# toucanRev2.net
KiCad netlist of a schematic drawn in EAGLE
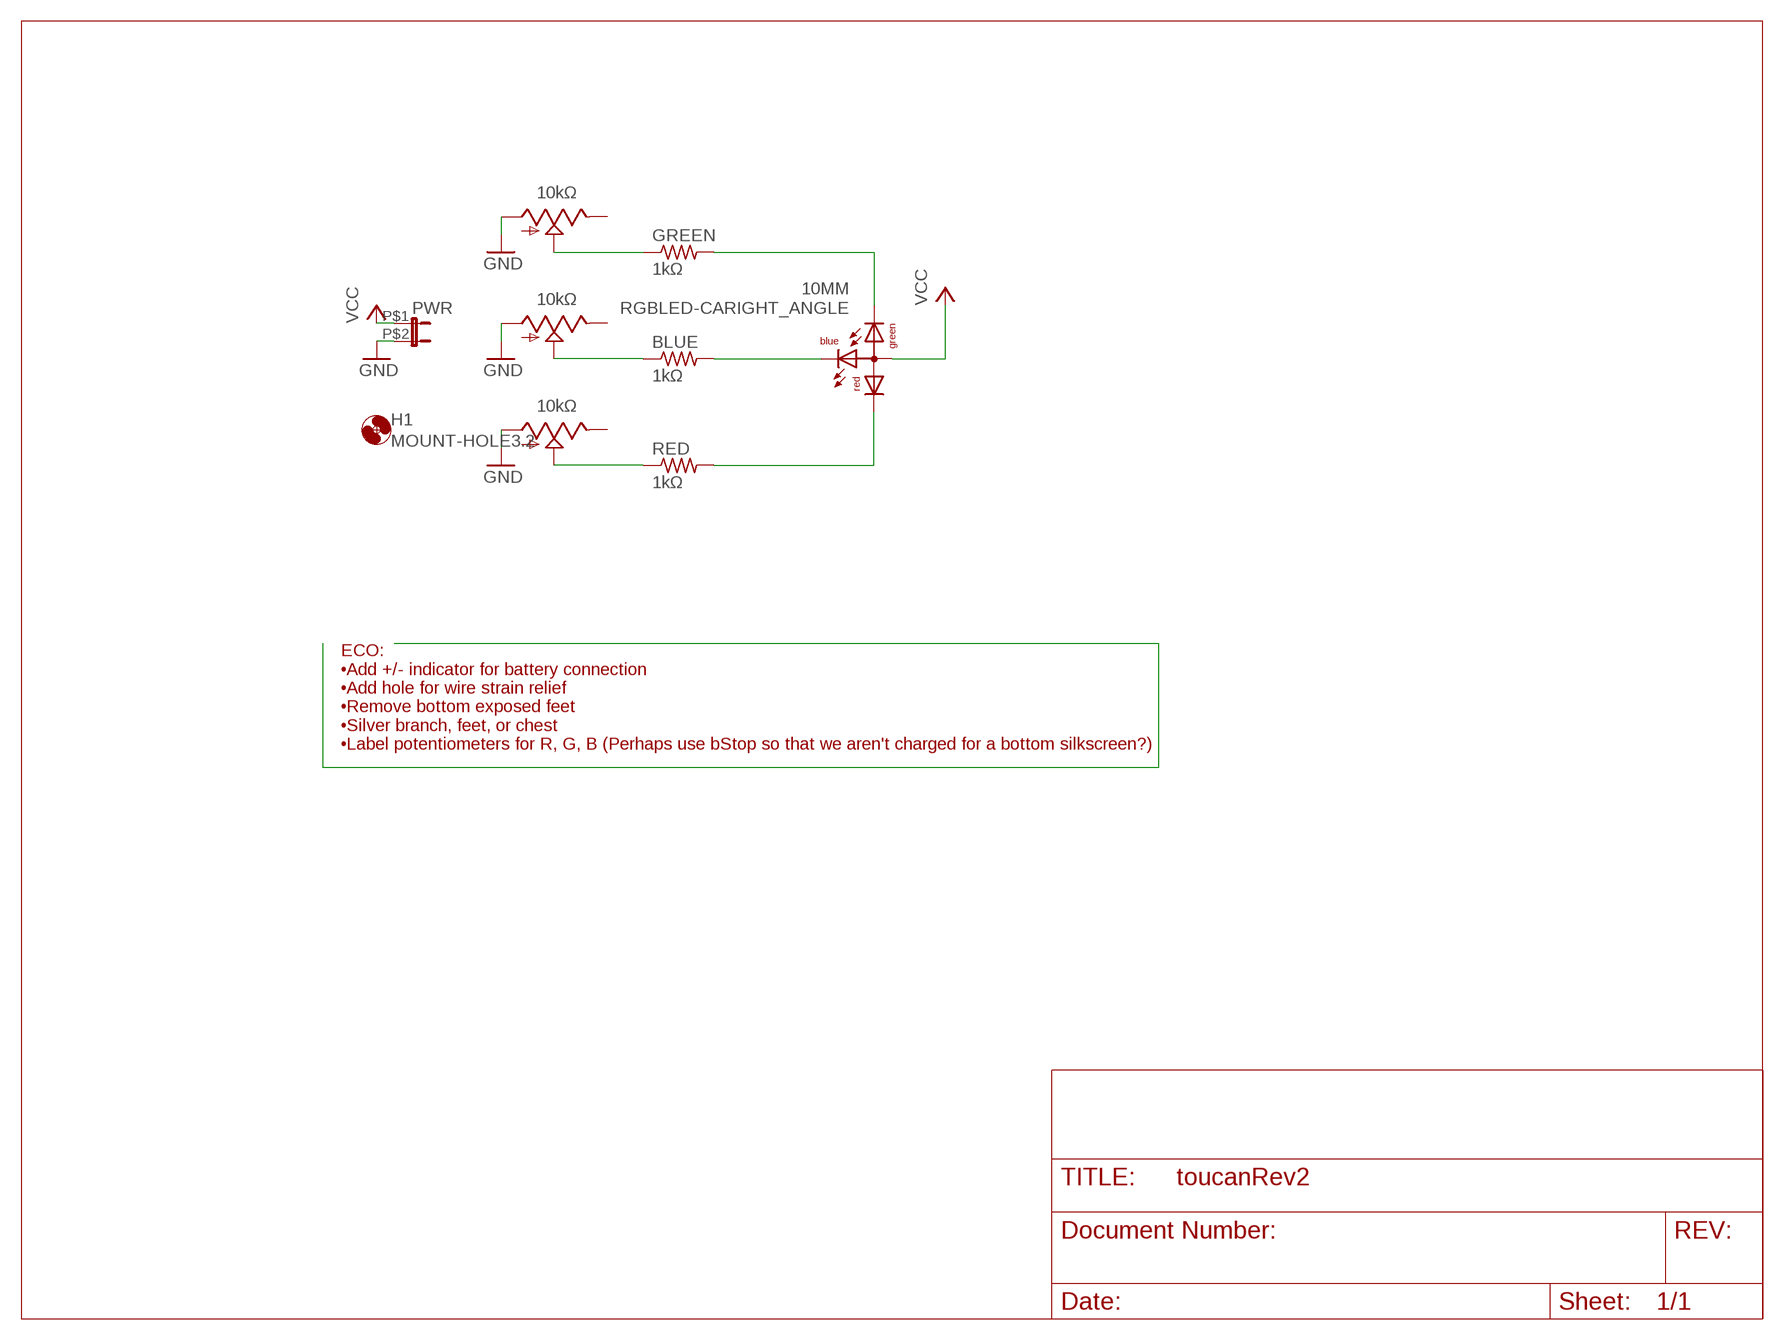
[diagram p0: schematic, sheet 1]

(export (version "E")
  (design (tool "Eeschema 10.0.6"))
  (components
    (comp (ref "10MM")
      (value "RGBLED-CARIGHT_ANGLE")
      (footprint "eagle-import:RGB10MM_FLAT")
      (libsource (lib "eagle-import") (part "RGBLED-CARIGHT_ANGLE"))
    )
    (comp (ref "BLUE")
      (value "1kΩ")
      (footprint "eagle-import:0207_12")
      (libsource (lib "eagle-import") (part "RESISTOR"))
    )
    (comp (ref "GREEN")
      (value "1kΩ")
      (footprint "eagle-import:0207_12")
      (libsource (lib "eagle-import") (part "RESISTOR"))
    )
    (comp (ref "H1")
      (value "MOUNT-HOLE3.2")
      (footprint "eagle-import:3,2")
      (libsource (lib "eagle-import") (part "MOUNT-HOLE3.2"))
    )
    (comp (ref "PWR")
      (value "2POS_HEADERJUMPER")
      (footprint "eagle-import:2HEADER")
      (libsource (lib "eagle-import") (part "2POS_HEADERJUMPER"))
    )
    (comp (ref "RED")
      (value "1kΩ")
      (footprint "eagle-import:0207_12")
      (libsource (lib "eagle-import") (part "RESISTOR"))
    )
    (comp (ref "U$2")
      (value "10kΩ")
      (footprint "eagle-import:S63P")
      (libsource (lib "eagle-import") (part "POTBOURNS"))
    )
    (comp (ref "U$4")
      (value "10kΩ")
      (footprint "eagle-import:S63P")
      (libsource (lib "eagle-import") (part "POTBOURNS"))
    )
    (comp (ref "U$5")
      (value "10kΩ")
      (footprint "eagle-import:S63P")
      (libsource (lib "eagle-import") (part "POTBOURNS"))
    )
  )
  (nets
    (net (code "1") (name "GND") (class "Default")
      (node (ref "PWR") (pin "P$2") (pinfunction "2_P$2") (pintype "passive"))
      (node (ref "U$2") (pin "LEFT") (pinfunction "A_LEFT") (pintype "passive"))
      (node (ref "U$4") (pin "LEFT") (pinfunction "A_LEFT") (pintype "passive"))
      (node (ref "U$5") (pin "LEFT") (pinfunction "A_LEFT") (pintype "passive"))
    )
    (net (code "2") (name "Net-(10MM-AB_PIN4)") (class "Default")
      (node (ref "10MM") (pin "PIN4") (pinfunction "AB_PIN4_PIN4") (pintype "passive"))
      (node (ref "BLUE") (pin "2") (pinfunction "2_2") (pintype "passive"))
    )
    (net (code "3") (name "Net-(10MM-AG_PIN3)") (class "Default")
      (node (ref "10MM") (pin "PIN3") (pinfunction "AG_PIN3_PIN3") (pintype "passive"))
      (node (ref "GREEN") (pin "2") (pinfunction "2_2") (pintype "passive"))
    )
    (net (code "4") (name "Net-(10MM-AR_PIN1)") (class "Default")
      (node (ref "10MM") (pin "PIN1") (pinfunction "AR_PIN1_PIN1") (pintype "passive"))
      (node (ref "RED") (pin "2") (pinfunction "2_2") (pintype "passive"))
    )
    (net (code "5") (name "Net-(U$2-S)") (class "Default")
      (node (ref "GREEN") (pin "1") (pinfunction "1_1") (pintype "passive"))
      (node (ref "U$2") (pin "CENTER") (pinfunction "S_CENTER") (pintype "passive"))
    )
    (net (code "6") (name "Net-(U$4-S)") (class "Default")
      (node (ref "BLUE") (pin "1") (pinfunction "1_1") (pintype "passive"))
      (node (ref "U$4") (pin "CENTER") (pinfunction "S_CENTER") (pintype "passive"))
    )
    (net (code "7") (name "Net-(U$5-S)") (class "Default")
      (node (ref "RED") (pin "1") (pinfunction "1_1") (pintype "passive"))
      (node (ref "U$5") (pin "CENTER") (pinfunction "S_CENTER") (pintype "passive"))
    )
    (net (code "8") (name "VCC") (class "Default")
      (node (ref "10MM") (pin "PIN2") (pinfunction "C_PIN2_PIN2") (pintype "passive"))
      (node (ref "PWR") (pin "P$1") (pinfunction "1_P$1") (pintype "passive"))
    )
    (net (code "9") (name "unconnected-(U$2-E-PadRIGHT)") (class "Default")
      (node (ref "U$2") (pin "RIGHT") (pinfunction "E_RIGHT") (pintype "passive"))
    )
    (net (code "10") (name "unconnected-(U$4-E-PadRIGHT)") (class "Default")
      (node (ref "U$4") (pin "RIGHT") (pinfunction "E_RIGHT") (pintype "passive"))
    )
    (net (code "11") (name "unconnected-(U$5-E-PadRIGHT)") (class "Default")
      (node (ref "U$5") (pin "RIGHT") (pinfunction "E_RIGHT") (pintype "passive"))
    )
  )
)
